# Sheet1.net
KiCad netlist of a schematic drawn in Altium Designer
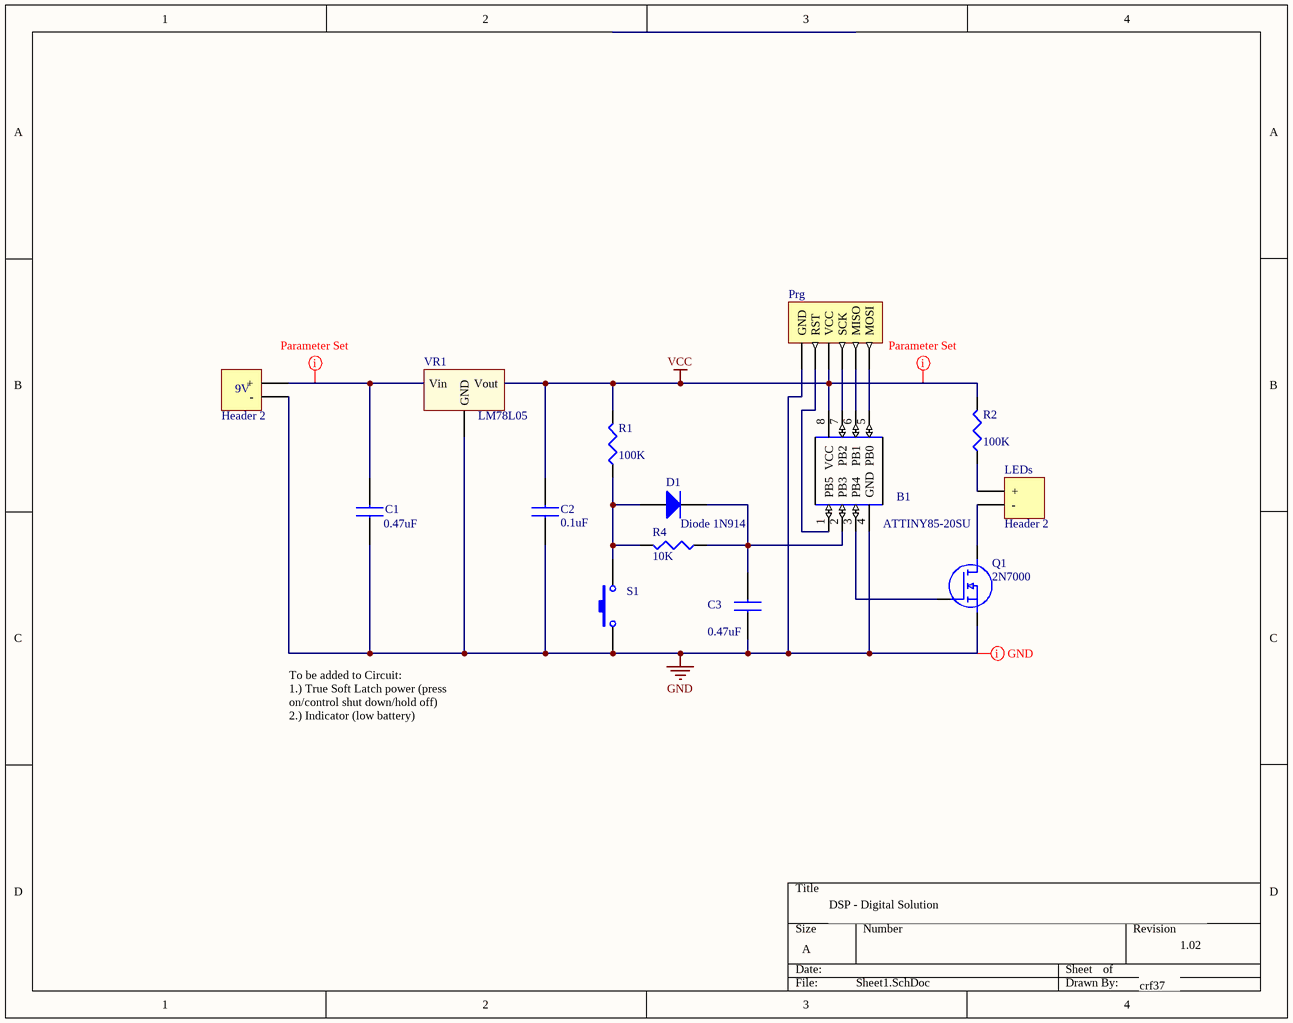
[diagram p0: Sheet1.SchDoc]

(export (version "E")
  (design (tool "Eeschema 10.0.6"))
  (components
    (comp (ref "9V")
      (value "Header 2")
      (footprint "HDR1X2")
      (description "Header, 2-Pin")
      (fields (field (name "PUBLISHER") "Altium Limited"))
      (libsource (lib "") (part "Header 2_1"))
    )
    (comp (ref "B1")
      (value "ATTINY85-20SU")
      (footprint "SOT127P798X216-8N")
      (description "MICROCHIP - ATTINY85-20SU - MICROCONTROLLER MCU, 8 BIT, ATTINY, 20MHZ, SOIC-8")
      (fields (field (name "RS PART NUMBER") "1331674"))
      (libsource (lib "ATTINY85-20SU") (part "ATTINY85-20SU"))
    )
    (comp (ref "C1")
      (value "0.47uF")
      (footprint "CAPC2012X145N")
      (description "Multilayer Ceramic Capacitors MLCC - SMD/SMT 0805 0.47uF 50volts X7R 10%")
      (fields
        (field (name "MANUFACTURER_PART_NUMBER") "GRM21BR71H474KA88L")
        (field (name "RS PART NUMBER") "7236118P")
      )
      (libsource (lib "GRM21BR71H474KA88L") (part "GRM21BR71H474KA88L"))
    )
    (comp (ref "C2")
      (value "0.1uF")
      (footprint "CAPC2012X145N")
      (description "Multilayer Ceramic Capacitors MLCC - SMD/SMT 0805 0.47uF 50volts X7R 10%")
      (fields
        (field (name "MANUFACTURER_PART_NUMBER") "GRM21BR71H474KA88L")
        (field (name "RS PART NUMBER") "7236118P")
      )
      (libsource (lib "GRM21BR71H474KA88L") (part "GRM21BR71H474KA88L"))
    )
    (comp (ref "C3")
      (value "0.47uF")
      (footprint "CAPC2012X145N")
      (description "Multilayer Ceramic Capacitors MLCC - SMD/SMT 0805 0.47uF 50volts X7R 10%")
      (fields
        (field (name "MANUFACTURER_PART_NUMBER") "GRM21BR71H474KA88L")
        (field (name "RS PART NUMBER") "7236118P")
      )
      (libsource (lib "GRM21BR71H474KA88L") (part "GRM21BR71H474KA88L"))
    )
    (comp (ref "D1")
      (value "Diode 1N914")
      (footprint "DO-35")
      (description "High Conductance Fast Diode")
      (fields (field (name "PUBLISHER") "Altium Limited"))
      (libsource (lib "Miscellaneous Devices") (part "Diode 1N914"))
    )
    (comp (ref "LEDs")
      (value "Header 2")
      (footprint "HDR1X2")
      (description "Header, 2-Pin")
      (fields (field (name "PUBLISHER") "Altium Limited"))
      (libsource (lib "Miscellaneous Connectors") (part "Header 2"))
    )
    (comp (ref "Prg")
      (value "Header 6")
      (footprint "HDR1X6")
      (description "Header, 6-Pin")
      (fields (field (name "PUBLISHER") "Altium Limited"))
      (libsource (lib "Miscellaneous Connectors") (part "Header 6"))
    )
    (comp (ref "Q1")
      (value "2N7000")
      (footprint "TO-92_(TO-226)")
      (description "N-channel MOSFET,2N7000 0.2A 60V")
      (fields (field (name "RS PART NUMBER") "1698553"))
      (libsource (lib "2N7000") (part "2N7000"))
    )
    (comp (ref "R1")
      (value "100K")
      (footprint "J1-0603")
      (description "Resistor")
      (fields (field (name "Comment") "Res3") (field (name "PUBLISHER") "Altium Limited"))
      (libsource (lib "Miscellaneous Devices") (part "Res3"))
    )
    (comp (ref "R2")
      (value "100K")
      (footprint "J1-0603")
      (description "Resistor")
      (fields (field (name "Comment") "Res3") (field (name "PUBLISHER") "Altium Limited"))
      (libsource (lib "") (part "Res3_1"))
    )
    (comp (ref "R4")
      (value "10K")
      (footprint "J1-0603")
      (description "Resistor")
      (fields (field (name "Comment") "Res3") (field (name "PUBLISHER") "Altium Limited"))
      (libsource (lib "Miscellaneous Devices") (part "Res3"))
    )
    (comp (ref "S1")
      (value "SW-PB")
      (footprint "SPST-2")
      (description "Switch")
      (fields (field (name "PUBLISHER") "Altium Limited"))
      (libsource (lib "Miscellaneous Devices") (part "SW-PB"))
    )
    (comp (ref "VR1")
      (value "LM78L05")
      (footprint "LP0003A")
      (description "Voltage regulator,LM78L05ACZ 5V LM78L05ACZ/NOPB, Voltage Regulator, 0.1A 5 V,")
      (fields
        (field (name "MANUFACTURER_PART_NUMBER") "LM78L05ACZ/NOPB")
        (field (name "RS PART NUMBER") "5359975P")
      )
      (libsource (lib "LM78L05ACZ_NOPB") (part "LM78L05"))
    )
  )
  (nets
    (net (code "1") (name "GND") (class "Default")
      (node (ref "9V") (pin "1") (pinfunction "-_1") (pintype "passive"))
      (node (ref "B1") (pin "4") (pinfunction "GND_4") (pintype "passive"))
      (node (ref "C1") (pin "1") (pinfunction "1_1") (pintype "passive"))
      (node (ref "C2") (pin "1") (pinfunction "1_1") (pintype "passive"))
      (node (ref "C3") (pin "1") (pinfunction "1_1") (pintype "passive"))
      (node (ref "Prg") (pin "1") (pinfunction "GND_1") (pintype "passive"))
      (node (ref "Q1") (pin "1") (pinfunction "S_1") (pintype "passive"))
      (node (ref "S1") (pin "1") (pinfunction "1_1") (pintype "passive"))
      (node (ref "VR1") (pin "2") (pinfunction "GND_2") (pintype "passive"))
    )
    (net (code "2") (name "Net-(9V-+)") (class "Default")
      (node (ref "9V") (pin "2") (pinfunction "+_2") (pintype "passive"))
      (node (ref "C1") (pin "2") (pinfunction "2_2") (pintype "passive"))
      (node (ref "VR1") (pin "3") (pinfunction "Vin_3") (pintype "passive"))
    )
    (net (code "3") (name "Net-(B1-PB0)") (class "Default")
      (node (ref "B1") (pin "5") (pinfunction "PB0_5") (pintype "bidirectional"))
      (node (ref "Prg") (pin "6") (pinfunction "MOSI_6") (pintype "output"))
    )
    (net (code "4") (name "Net-(B1-PB1)") (class "Default")
      (node (ref "B1") (pin "6") (pinfunction "PB1_6") (pintype "bidirectional"))
      (node (ref "Prg") (pin "5") (pinfunction "MISO_5") (pintype "output"))
    )
    (net (code "5") (name "Net-(B1-PB2)") (class "Default")
      (node (ref "B1") (pin "7") (pinfunction "PB2_7") (pintype "bidirectional"))
      (node (ref "Prg") (pin "4") (pinfunction "SCK_4") (pintype "output"))
    )
    (net (code "6") (name "Net-(B1-PB3)") (class "Default")
      (node (ref "B1") (pin "2") (pinfunction "PB3_2") (pintype "bidirectional"))
      (node (ref "C3") (pin "2") (pinfunction "2_2") (pintype "passive"))
      (node (ref "D1") (pin "2") (pinfunction "K_2") (pintype "passive"))
      (node (ref "R4") (pin "1") (pinfunction "1_1") (pintype "passive"))
    )
    (net (code "7") (name "Net-(B1-PB4)") (class "Default")
      (node (ref "B1") (pin "3") (pinfunction "PB4_3") (pintype "bidirectional"))
      (node (ref "Q1") (pin "2") (pinfunction "G_2") (pintype "passive"))
    )
    (net (code "8") (name "Net-(B1-PB5)") (class "Default")
      (node (ref "B1") (pin "1") (pinfunction "PB5_1") (pintype "bidirectional"))
      (node (ref "Prg") (pin "2") (pinfunction "RST_2") (pintype "output"))
    )
    (net (code "9") (name "Net-(D1-A)") (class "Default")
      (node (ref "D1") (pin "1") (pinfunction "A_1") (pintype "passive"))
      (node (ref "R1") (pin "1") (pinfunction "1_1") (pintype "passive"))
      (node (ref "R4") (pin "2") (pinfunction "2_2") (pintype "passive"))
      (node (ref "S1") (pin "2") (pinfunction "2_2") (pintype "passive"))
    )
    (net (code "10") (name "Net-(LEDs-+)") (class "Default")
      (node (ref "LEDs") (pin "1") (pinfunction "+_1") (pintype "passive"))
      (node (ref "R2") (pin "2") (pinfunction "2_2") (pintype "passive"))
    )
    (net (code "11") (name "Net-(LEDs--)") (class "Default")
      (node (ref "LEDs") (pin "2") (pinfunction "-_2") (pintype "passive"))
      (node (ref "Q1") (pin "3") (pinfunction "D_3") (pintype "passive"))
    )
    (net (code "12") (name "VCC") (class "Default")
      (node (ref "B1") (pin "8") (pinfunction "VCC_8") (pintype "power_in"))
      (node (ref "C2") (pin "2") (pinfunction "2_2") (pintype "passive"))
      (node (ref "Prg") (pin "3") (pinfunction "VCC_3") (pintype "power_in"))
      (node (ref "R1") (pin "2") (pinfunction "2_2") (pintype "passive"))
      (node (ref "R2") (pin "2") (pinfunction "2_2") (pintype "passive"))
      (node (ref "VR1") (pin "1") (pinfunction "Vout_1") (pintype "passive"))
    )
  )
)
